# SH1_-_POWER.net
KiCad netlist of a schematic drawn in Altium Designer
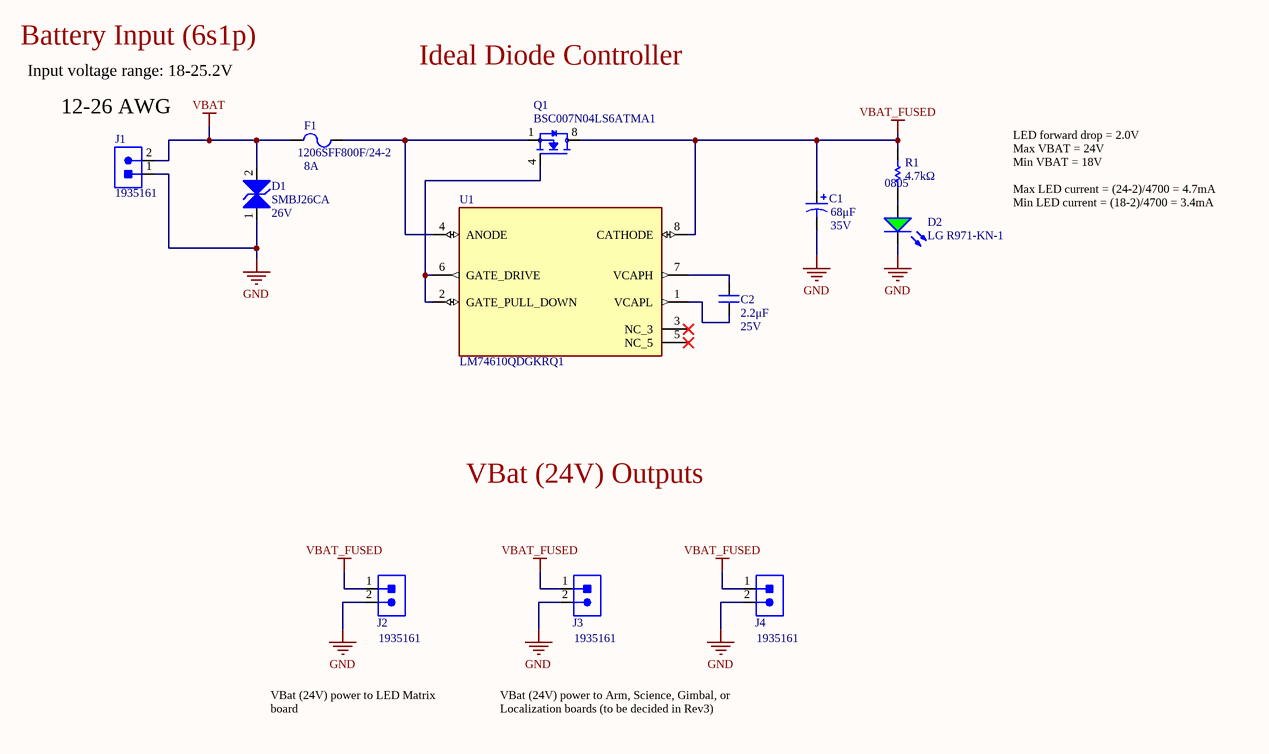
[diagram p0: SH1 - POWER.SchDoc]

(export (version "E")
  (design (tool "Eeschema 10.0.6"))
  (components
    (comp (ref "C1")
      (value "68μF")
      (footprint "RADIAL_NICHION_1V")
      (description "CAP ALUM 68UF 20% 35V SMD")
      (fields
        (field (name "TOLERANCE") "20%")
        (field (name "VOLTAGE RATING") "35V")
        (field (name "Comment") "CAP_68uF_35V_ALUM")
      )
      (libsource (lib "UWRT_Schematic_Library_2020") (part "CAP_68uF_35V_ALUM"))
    )
    (comp (ref "C2")
      (value "2.2μF")
      (footprint "CAP2012")
      (description "CAP CER 2.2UF 25V X7R 0805")
      (fields
        (field (name "VOLTAGE RATING") "25V")
        (field (name "LCSC PART #") "C49217")
        (field (name "Comment") "CAP_2.2uF_25V_0805")
      )
      (libsource (lib "UWRT_Schematic_Library_2020") (part "CAP_2.2uF_25V_0805"))
    )
    (comp (ref "D1")
      (value "TVS_DIODE_BIDIR_26V")
      (footprint "TVS_DIODE_BIDIRECTIONAL")
      (description "TVS DIODE 26V 42.1V DO214AA")
      (fields
        (field (name "MANUFACTURER PART NUMBER 1") "SMBJ26CA")
        (field (name "REVERSE STANDOFF VOLTAGE") "26V")
        (field (name "LCSC PART #") "C8835")
      )
      (libsource (lib "UWRT_Schematic_Library_2020") (part "TVS_DIODE_BIDIR_26V"))
    )
    (comp (ref "D2")
      (value "DIO_LED_G")
      (footprint "LED_0805_GREEN")
      (description "LED GREEN DIFFUSED 0805 SMD")
      (fields (field (name "MANUFACTURER PART NUMBER 1") "LG R971-KN-1"))
      (libsource (lib "UWRT_Schematic_Library_2020") (part "DIO_LED_G"))
    )
    (comp (ref "F1")
      (value "FUSE_8A_1206")
      (footprint "FUSE_1206")
      (description "FUSE SMD 8A 24V")
      (fields
        (field (name "MANUFACTURER PART NUMBER 1") "1206SFF800F/24-2")
        (field (name "CURRENT RATING") "8A")
        (field (name "LCSC PART #") "C311032")
      )
      (libsource (lib "UWRT_Schematic_Library_2020") (part "FUSE_8A_1206"))
    )
    (comp (ref "J1")
      (value "CON_2M_TERM")
      (footprint "1935161")
      (description "TERM BLK 2POS SIDE ENTRY 5MM")
      (fields (field (name "VOLTAGE") "300V") (field (name "MANUFACTURER PART NUMBER 1") "1935161"))
      (libsource (lib "") (part "CON_2M_TERM_1"))
    )
    (comp (ref "J2")
      (value "CON_2M_TERM")
      (footprint "1935161")
      (description "TERM BLK 2POS SIDE ENTRY 5MM")
      (fields (field (name "VOLTAGE") "300V") (field (name "MANUFACTURER PART NUMBER 1") "1935161"))
      (libsource (lib "UWRT_Schematic_Library_2020") (part "CON_2M_TERM"))
    )
    (comp (ref "J3")
      (value "CON_2M_TERM")
      (footprint "1935161")
      (description "TERM BLK 2POS SIDE ENTRY 5MM")
      (fields (field (name "VOLTAGE") "300V") (field (name "MANUFACTURER PART NUMBER 1") "1935161"))
      (libsource (lib "UWRT_Schematic_Library_2020") (part "CON_2M_TERM"))
    )
    (comp (ref "J4")
      (value "CON_2M_TERM")
      (footprint "1935161")
      (description "TERM BLK 2POS SIDE ENTRY 5MM")
      (fields (field (name "VOLTAGE") "300V") (field (name "MANUFACTURER PART NUMBER 1") "1935161"))
      (libsource (lib "UWRT_Schematic_Library_2020") (part "CON_2M_TERM"))
    )
    (comp (ref "Q1")
      (value "NMOS_40V_100A")
      (footprint "TRANS_BSC007N04LS6ATMA1")
      (description "N-Channel 40V 100A 188W Surface Mount PG-TDSON-8-6")
      (fields (field (name "MANUFACTURER PART NUMBER 1") "BSC007N04LS6ATMA1"))
      (libsource (lib "UWRT_Schematic_Library_2020") (part "NMOS_40V_100A"))
    )
    (comp (ref "R1")
      (value "4.7kΩ")
      (footprint "RESC0805")
      (description "RES 4.7K OHM 5% 1/8W 0805")
      (fields
        (field (name "LCSC PART #") "C17673")
        (field (name "PACKAGE/FOOTPRINT") "0805")
        (field (name "Comment") "RES_4.7kΩ_0805_5%")
      )
      (libsource (lib "UWRT_Schematic_Library_2020") (part "RES_4.7kΩ_0805_5%"))
    )
    (comp (ref "U1")
      (value "LM74610QDGKRQ1")
      (footprint "UWRT_Footprint_Library_2020:SOP65P490X110-8N")
      (description "IC SMART DIODE CTLR 8VSSOP")
      (fields (field (name "LCSC PART #") "C202259"))
      (libsource (lib "UWRT_Schematic_Library_2020") (part "LM74610QDGKRQ1"))
    )
  )
  (nets
    (net (code "1") (name "GND") (class "Default")
      (node (ref "C1") (pin "2") (pinfunction "2_2") (pintype "passive"))
      (node (ref "D1") (pin "1") (pinfunction "1_1") (pintype "passive"))
      (node (ref "D2") (pin "2") (pinfunction "K_2") (pintype "passive"))
      (node (ref "J1") (pin "1") (pinfunction "1_1") (pintype "passive"))
      (node (ref "J2") (pin "2") (pinfunction "2_2") (pintype "passive"))
      (node (ref "J3") (pin "2") (pinfunction "2_2") (pintype "passive"))
      (node (ref "J4") (pin "2") (pinfunction "2_2") (pintype "passive"))
    )
    (net (code "2") (name "Net-(D2-A)") (class "Default")
      (node (ref "D2") (pin "1") (pinfunction "A_1") (pintype "passive"))
      (node (ref "R1") (pin "1") (pinfunction "1_1") (pintype "passive"))
    )
    (net (code "3") (name "Net-(Q1-G)") (class "Default")
      (node (ref "Q1") (pin "4") (pinfunction "G_4") (pintype "passive"))
      (node (ref "U1") (pin "2") (pinfunction "GATE_PULL_DOWN_2") (pintype "bidirectional"))
      (node (ref "U1") (pin "6") (pinfunction "GATE_DRIVE_6") (pintype "output"))
    )
    (net (code "4") (name "Net-(Q1-S)") (class "Default")
      (node (ref "F1") (pin "2") (pinfunction "2_2") (pintype "passive"))
      (node (ref "Q1") (pin "1") (pinfunction "S_1") (pintype "passive"))
      (node (ref "U1") (pin "4") (pinfunction "ANODE_4") (pintype "bidirectional"))
    )
    (net (code "5") (name "Net-(U1-VCAPH)") (class "Default")
      (node (ref "C2") (pin "2") (pinfunction "2_2") (pintype "passive"))
      (node (ref "U1") (pin "7") (pinfunction "VCAPH_7") (pintype "output"))
    )
    (net (code "6") (name "Net-(U1-VCAPL)") (class "Default")
      (node (ref "C2") (pin "1") (pinfunction "1_1") (pintype "passive"))
      (node (ref "U1") (pin "1") (pinfunction "VCAPL_1") (pintype "output"))
    )
    (net (code "7") (name "VBAT") (class "Default")
      (node (ref "D1") (pin "2") (pinfunction "2_2") (pintype "passive"))
      (node (ref "F1") (pin "1") (pinfunction "1_1") (pintype "passive"))
      (node (ref "J1") (pin "2") (pinfunction "2_2") (pintype "passive"))
    )
    (net (code "8") (name "VBAT_FUSED") (class "Default")
      (node (ref "C1") (pin "1") (pinfunction "1_1") (pintype "passive"))
      (node (ref "J2") (pin "1") (pinfunction "1_1") (pintype "passive"))
      (node (ref "J3") (pin "1") (pinfunction "1_1") (pintype "passive"))
      (node (ref "J4") (pin "1") (pinfunction "1_1") (pintype "passive"))
      (node (ref "Q1") (pin "8") (pinfunction "D_8") (pintype "passive"))
      (node (ref "R1") (pin "2") (pinfunction "2_2") (pintype "passive"))
      (node (ref "U1") (pin "8") (pinfunction "CATHODE_8") (pintype "bidirectional"))
    )
    (net (code "9") (name "unconnected-(U1-NC_3-Pad3)") (class "Default")
      (node (ref "U1") (pin "3") (pinfunction "NC_3_3") (pintype "passive+no_connect"))
    )
    (net (code "10") (name "unconnected-(U1-NC_5-Pad5)") (class "Default")
      (node (ref "U1") (pin "5") (pinfunction "NC_5_5") (pintype "passive+no_connect"))
    )
  )
)
